# SENSOR.net
KiCad netlist of a schematic drawn in Altium Designer
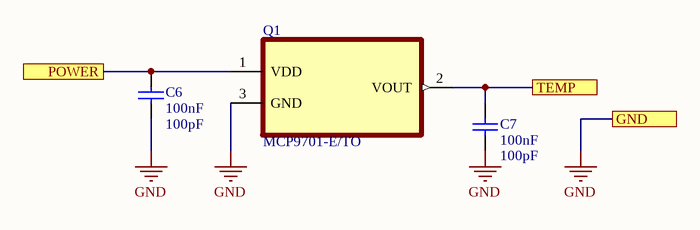
[diagram p0: SENSOR.SchDoc]

(export (version "E")
  (design (tool "Eeschema 10.0.6"))
  (components
    (comp (ref "C6")
      (value "100nF")
      (footprint "RAD-0.3")
      (description "Capacitor")
      (fields (field (name "ALTIUM_VALUE") "100pF") (field (name "PUBLISHER") "Altium Limited"))
      (libsource (lib "Miscellaneous Devices") (part "Cap"))
    )
    (comp (ref "C7")
      (value "100nF")
      (footprint "RAD-0.3")
      (description "Capacitor")
      (fields (field (name "ALTIUM_VALUE") "100pF") (field (name "PUBLISHER") "Altium Limited"))
      (libsource (lib "Miscellaneous Devices") (part "Cap"))
    )
    (comp (ref "Q1")
      (value "MCP9701-E/TO")
      (footprint "TO127P254X533-3")
      (fields (field (name "MF") "Microchip Technology"))
      (libsource (lib "SENSOR_TEMPERATURA") (part "MCP9701-E/TO"))
    )
  )
  (nets
    (net (code "1") (name "/POWER") (class "Default")
      (node (ref "C6") (pin "1") (pinfunction "1_1") (pintype "passive"))
      (node (ref "Q1") (pin "1") (pinfunction "VDD_1") (pintype "power_in"))
    )
    (net (code "2") (name "/TEMP") (class "Default")
      (node (ref "C7") (pin "1") (pinfunction "1_1") (pintype "passive"))
      (node (ref "Q1") (pin "2") (pinfunction "VOUT_2") (pintype "output"))
    )
    (net (code "3") (name "GND") (class "Default")
      (node (ref "C6") (pin "2") (pinfunction "2_2") (pintype "passive"))
      (node (ref "C7") (pin "2") (pinfunction "2_2") (pintype "passive"))
      (node (ref "Q1") (pin "3") (pinfunction "GND_3") (pintype "passive"))
    )
  )
)
